# RFFE.net
KiCad netlist of a schematic drawn in Altium Designer
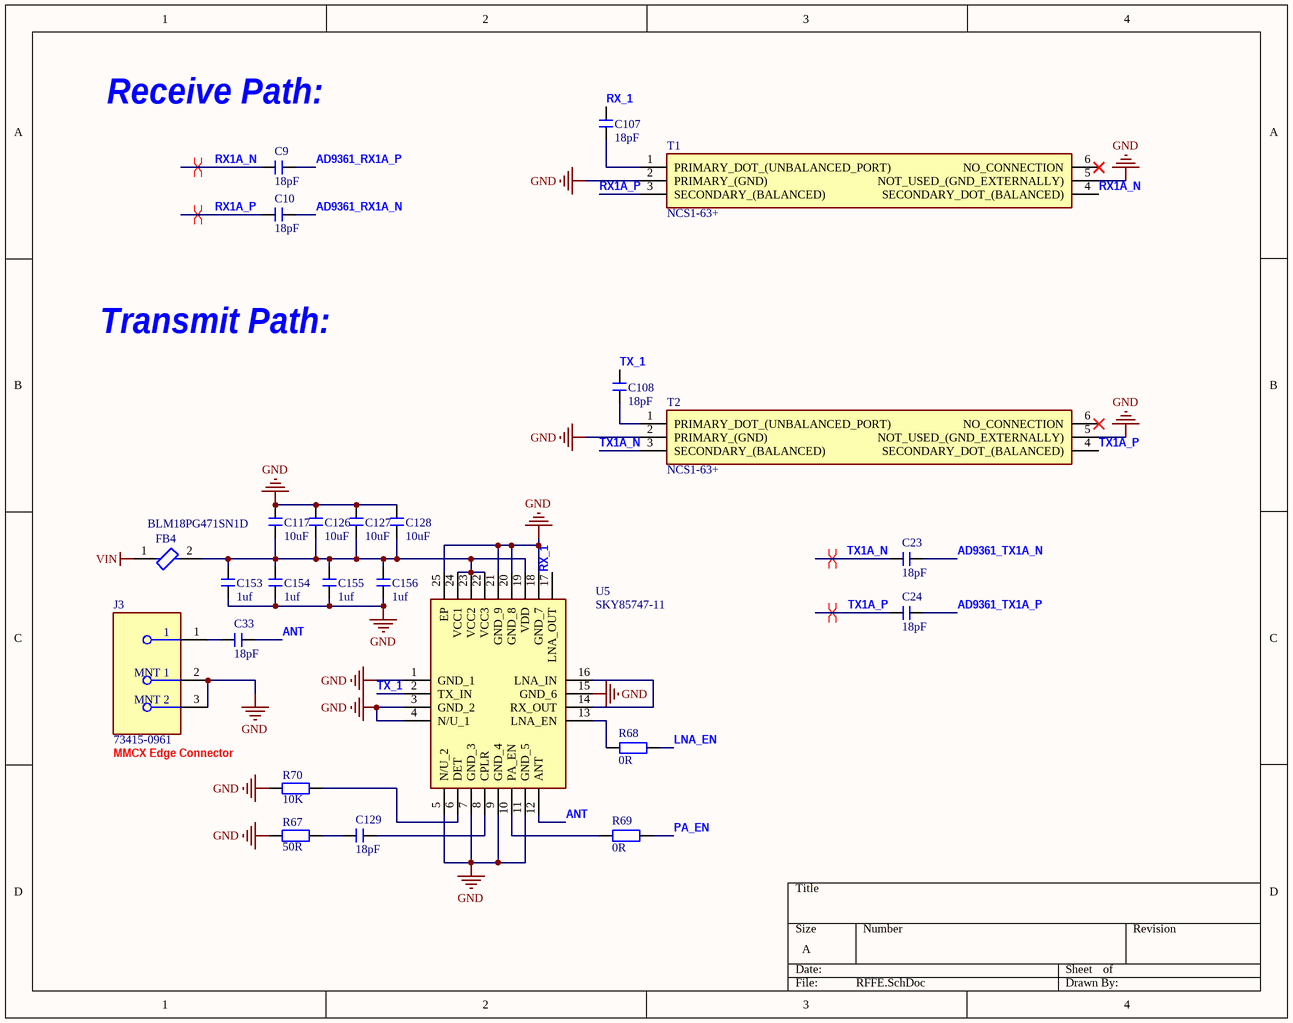
[diagram p0: RFFE.SchDoc]

(export (version "E")
  (design (tool "Eeschema 10.0.6"))
  (components
    (comp (ref "C9")
      (value "18pF")
      (footprint "SamacSys:CAP_0201")
      (description "无极性贴片电容")
      (fields (field (name "版权归属") "源创客"))
      (libsource (lib "源创客") (part "C"))
    )
    (comp (ref "C10")
      (value "18pF")
      (footprint "SamacSys:CAP_0201")
      (description "无极性贴片电容")
      (fields (field (name "版权归属") "源创客"))
      (libsource (lib "源创客") (part "C"))
    )
    (comp (ref "C23")
      (value "18pF")
      (footprint "SamacSys:CAP_0201")
      (description "无极性贴片电容")
      (fields (field (name "版权归属") "源创客"))
      (libsource (lib "源创客") (part "C"))
    )
    (comp (ref "C24")
      (value "18pF")
      (footprint "SamacSys:CAP_0201")
      (description "无极性贴片电容")
      (fields (field (name "版权归属") "源创客"))
      (libsource (lib "源创客") (part "C"))
    )
    (comp (ref "C33")
      (value "18pF")
      (footprint "SamacSys:CAP_0201")
      (description "无极性贴片电容")
      (fields (field (name "版权归属") "源创客"))
      (libsource (lib "源创客") (part "C"))
    )
    (comp (ref "C107")
      (value "18pF")
      (footprint "SamacSys:CAP_0201")
      (description "无极性贴片电容")
      (fields (field (name "版权归属") "源创客"))
      (libsource (lib "源创客") (part "C"))
    )
    (comp (ref "C108")
      (value "18pF")
      (footprint "SamacSys:CAP_0201")
      (description "无极性贴片电容")
      (fields (field (name "版权归属") "源创客"))
      (libsource (lib "源创客") (part "C"))
    )
    (comp (ref "C117")
      (value "10uF")
      (footprint "SamacSys:CAP_0402")
      (description "无极性贴片电容")
      (fields (field (name "版权归属") "源创客"))
      (libsource (lib "源创客") (part "C"))
    )
    (comp (ref "C126")
      (value "10uF")
      (footprint "SamacSys:CAP_0402")
      (description "无极性贴片电容")
      (fields (field (name "版权归属") "源创客"))
      (libsource (lib "源创客") (part "C"))
    )
    (comp (ref "C127")
      (value "10uF")
      (footprint "SamacSys:CAP_0402")
      (description "无极性贴片电容")
      (fields (field (name "版权归属") "源创客"))
      (libsource (lib "源创客") (part "C"))
    )
    (comp (ref "C128")
      (value "10uF")
      (footprint "SamacSys:CAP_0402")
      (description "无极性贴片电容")
      (fields (field (name "版权归属") "源创客"))
      (libsource (lib "源创客") (part "C"))
    )
    (comp (ref "C129")
      (value "18pF")
      (footprint "SamacSys:CAP_0201")
      (description "无极性贴片电容")
      (fields (field (name "版权归属") "源创客"))
      (libsource (lib "源创客") (part "C"))
    )
    (comp (ref "C153")
      (value "1uf")
      (footprint "SamacSys:CAP_0201")
      (description "无极性贴片电容")
      (fields (field (name "版权归属") "源创客"))
      (libsource (lib "源创客") (part "C"))
    )
    (comp (ref "C154")
      (value "1uf")
      (footprint "SamacSys:CAP_0201")
      (description "无极性贴片电容")
      (fields (field (name "版权归属") "源创客"))
      (libsource (lib "源创客") (part "C"))
    )
    (comp (ref "C155")
      (value "1uf")
      (footprint "SamacSys:CAP_0201")
      (description "无极性贴片电容")
      (fields (field (name "版权归属") "源创客"))
      (libsource (lib "源创客") (part "C"))
    )
    (comp (ref "C156")
      (value "1uf")
      (footprint "SamacSys:CAP_0201")
      (description "无极性贴片电容")
      (fields (field (name "版权归属") "源创客"))
      (libsource (lib "源创客") (part "C"))
    )
    (comp (ref "FB4")
      (value "BLM18PG471SN1D")
      (footprint "FP-BLM18-0_15-t0_8-MFG")
      (description "Chip Ferrite Bead, 0603, 470Ω @ 100MHz, 0.2Ω, 25%, 1A")
      (fields (field (name "TOLERANCE") "25%"))
      (libsource (lib "Altium Content Vault") (part "5f30dd21d616792df468990f7003faa"))
    )
    (comp (ref "J3")
      (value "73415-0961")
      (footprint "FP-73415-0961-MFG")
      (libsource (lib "Altium Content Vault") (part "89929399afe843c8b6880c6cbd0f99a"))
    )
    (comp (ref "R67")
      (value "50R")
      (footprint "SamacSys:RES_0201")
      (description "Resistor")
      (libsource (lib "源创客") (part "Resistor"))
    )
    (comp (ref "R68")
      (value "0R")
      (footprint "SamacSys:RES_0402")
      (description "贴片电阻")
      (fields (field (name "版权归属") "源创客"))
      (libsource (lib "源创客") (part "R"))
    )
    (comp (ref "R69")
      (value "0R")
      (footprint "SamacSys:RES_0402")
      (description "贴片电阻")
      (fields (field (name "版权归属") "源创客"))
      (libsource (lib "源创客") (part "R"))
    )
    (comp (ref "R70")
      (value "10K")
      (footprint "SamacSys:RES_0201")
      (description "Resistor")
      (libsource (lib "源创客") (part "Resistor"))
    )
    (comp (ref "T1")
      (value "NCS1-63+")
      (footprint "SamacSys:NCS163")
      (description "Transformer")
      (fields (field (name "MOUSER PART NUMBER") "139-NCS1-63"))
      (libsource (lib "*") (part "NCS1-63+"))
    )
    (comp (ref "T2")
      (value "NCS1-63+")
      (footprint "SamacSys:NCS163")
      (description "Transformer")
      (fields (field (name "MOUSER PART NUMBER") "139-NCS1-63"))
      (libsource (lib "*") (part "NCS1-63+"))
    )
    (comp (ref "U5")
      (value "SKY85747-11")
      (footprint "SamacSys:SKY8574711")
      (description "Integrated Circuit")
      (libsource (lib "*") (part "SKY85747-11"))
    )
  )
  (nets
    (net (code "1") (name "/AD9361_RX1A_N") (class "Default")
      (node (ref "C10") (pin "2") (pinfunction "2_2") (pintype "passive"))
    )
    (net (code "2") (name "/AD9361_RX1A_P") (class "Default")
      (node (ref "C9") (pin "2") (pinfunction "2_2") (pintype "passive"))
    )
    (net (code "3") (name "/AD9361_TX1A_N") (class "Default")
      (node (ref "C23") (pin "2") (pinfunction "2_2") (pintype "passive"))
    )
    (net (code "4") (name "/AD9361_TX1A_P") (class "Default")
      (node (ref "C24") (pin "2") (pinfunction "2_2") (pintype "passive"))
    )
    (net (code "5") (name "/ANT") (class "Default")
      (node (ref "C33") (pin "2") (pinfunction "2_2") (pintype "passive"))
      (node (ref "U5") (pin "12") (pinfunction "ANT_12") (pintype "passive"))
    )
    (net (code "6") (name "/LNA_EN") (class "Default")
      (node (ref "R68") (pin "1") (pinfunction "1_1") (pintype "passive"))
    )
    (net (code "7") (name "/PA_EN") (class "Default")
      (node (ref "R69") (pin "1") (pinfunction "1_1") (pintype "passive"))
    )
    (net (code "8") (name "/RX1A_N") (class "Default")
      (node (ref "C9") (pin "1") (pinfunction "1_1") (pintype "passive"))
      (node (ref "T1") (pin "4") (pinfunction "SECONDARY_DOT_(BALANCED)_4") (pintype "passive"))
    )
    (net (code "9") (name "/RX1A_P") (class "Default")
      (node (ref "C10") (pin "1") (pinfunction "1_1") (pintype "passive"))
      (node (ref "T1") (pin "3") (pinfunction "SECONDARY_(BALANCED)_3") (pintype "passive"))
    )
    (net (code "10") (name "/RX_1") (class "Default")
      (node (ref "C107") (pin "2") (pinfunction "2_2") (pintype "passive"))
      (node (ref "U5") (pin "17") (pinfunction "LNA_OUT_17") (pintype "passive"))
    )
    (net (code "11") (name "/TX1A_N") (class "Default")
      (node (ref "C23") (pin "1") (pinfunction "1_1") (pintype "passive"))
      (node (ref "T2") (pin "3") (pinfunction "SECONDARY_(BALANCED)_3") (pintype "passive"))
    )
    (net (code "12") (name "/TX1A_P") (class "Default")
      (node (ref "C24") (pin "1") (pinfunction "1_1") (pintype "passive"))
      (node (ref "T2") (pin "4") (pinfunction "SECONDARY_DOT_(BALANCED)_4") (pintype "passive"))
    )
    (net (code "13") (name "/TX_1") (class "Default")
      (node (ref "C108") (pin "2") (pinfunction "2_2") (pintype "passive"))
      (node (ref "U5") (pin "2") (pinfunction "TX_IN_2") (pintype "passive"))
    )
    (net (code "14") (name "GND") (class "Default")
      (node (ref "C117") (pin "2") (pinfunction "2_2") (pintype "passive"))
      (node (ref "C126") (pin "2") (pinfunction "2_2") (pintype "passive"))
      (node (ref "C127") (pin "2") (pinfunction "2_2") (pintype "passive"))
      (node (ref "C128") (pin "2") (pinfunction "2_2") (pintype "passive"))
      (node (ref "C153") (pin "1") (pinfunction "1_1") (pintype "passive"))
      (node (ref "C154") (pin "1") (pinfunction "1_1") (pintype "passive"))
      (node (ref "C155") (pin "1") (pinfunction "1_1") (pintype "passive"))
      (node (ref "C156") (pin "1") (pinfunction "1_1") (pintype "passive"))
      (node (ref "J3") (pin "2") (pinfunction "MNT_1_2") (pintype "passive"))
      (node (ref "J3") (pin "3") (pinfunction "MNT_2_3") (pintype "passive"))
      (node (ref "R67") (pin "2") (pinfunction "2_2") (pintype "passive"))
      (node (ref "R70") (pin "2") (pinfunction "2_2") (pintype "passive"))
      (node (ref "T1") (pin "2") (pinfunction "PRIMARY_(GND)_2") (pintype "passive"))
      (node (ref "T1") (pin "5") (pinfunction "NOT_USED_(GND_EXTERNALLY)_5") (pintype "passive"))
      (node (ref "T2") (pin "2") (pinfunction "PRIMARY_(GND)_2") (pintype "passive"))
      (node (ref "T2") (pin "5") (pinfunction "NOT_USED_(GND_EXTERNALLY)_5") (pintype "passive"))
      (node (ref "U5") (pin "1") (pinfunction "GND_1_1") (pintype "passive"))
      (node (ref "U5") (pin "11") (pinfunction "GND_5_11") (pintype "passive"))
      (node (ref "U5") (pin "15") (pinfunction "GND_6_15") (pintype "passive"))
      (node (ref "U5") (pin "18") (pinfunction "GND_7_18") (pintype "passive"))
      (node (ref "U5") (pin "20") (pinfunction "GND_8_20") (pintype "passive"))
      (node (ref "U5") (pin "21") (pinfunction "GND_9_21") (pintype "passive"))
      (node (ref "U5") (pin "25") (pinfunction "EP_25") (pintype "passive"))
      (node (ref "U5") (pin "3") (pinfunction "GND_2_3") (pintype "passive"))
      (node (ref "U5") (pin "4") (pinfunction "N/U_1_4") (pintype "passive"))
      (node (ref "U5") (pin "5") (pinfunction "N/U_2_5") (pintype "passive"))
      (node (ref "U5") (pin "7") (pinfunction "GND_3_7") (pintype "passive"))
      (node (ref "U5") (pin "9") (pinfunction "GND_4_9") (pintype "passive"))
    )
    (net (code "15") (name "Net-(C33-Pad1)") (class "Default")
      (node (ref "C33") (pin "1") (pinfunction "1_1") (pintype "passive"))
      (node (ref "J3") (pin "1") (pinfunction "1_1") (pintype "passive"))
    )
    (net (code "16") (name "Net-(C129-Pad1)") (class "Default")
      (node (ref "C129") (pin "1") (pinfunction "1_1") (pintype "passive"))
      (node (ref "R67") (pin "1") (pinfunction "1_1") (pintype "passive"))
    )
    (net (code "17") (name "Net-(T1-PRIMARY_DOT_(UNBALANCED_PORT))") (class "Default")
      (node (ref "C107") (pin "1") (pinfunction "1_1") (pintype "passive"))
      (node (ref "T1") (pin "1") (pinfunction "PRIMARY_DOT_(UNBALANCED_PORT)_1") (pintype "passive"))
    )
    (net (code "18") (name "Net-(T2-PRIMARY_DOT_(UNBALANCED_PORT))") (class "Default")
      (node (ref "C108") (pin "1") (pinfunction "1_1") (pintype "passive"))
      (node (ref "T2") (pin "1") (pinfunction "PRIMARY_DOT_(UNBALANCED_PORT)_1") (pintype "passive"))
    )
    (net (code "19") (name "Net-(U5-CPLR)") (class "Default")
      (node (ref "C129") (pin "2") (pinfunction "2_2") (pintype "passive"))
      (node (ref "U5") (pin "8") (pinfunction "CPLR_8") (pintype "passive"))
    )
    (net (code "20") (name "Net-(U5-DET)") (class "Default")
      (node (ref "R70") (pin "1") (pinfunction "1_1") (pintype "passive"))
      (node (ref "U5") (pin "6") (pinfunction "DET_6") (pintype "passive"))
    )
    (net (code "21") (name "Net-(U5-LNA_EN)") (class "Default")
      (node (ref "R68") (pin "2") (pinfunction "2_2") (pintype "passive"))
      (node (ref "U5") (pin "13") (pinfunction "LNA_EN_13") (pintype "passive"))
    )
    (net (code "22") (name "Net-(U5-LNA_IN)") (class "Default")
      (node (ref "U5") (pin "14") (pinfunction "RX_OUT_14") (pintype "passive"))
      (node (ref "U5") (pin "16") (pinfunction "LNA_IN_16") (pintype "passive"))
    )
    (net (code "23") (name "Net-(U5-PA_EN)") (class "Default")
      (node (ref "R69") (pin "2") (pinfunction "2_2") (pintype "passive"))
      (node (ref "U5") (pin "10") (pinfunction "PA_EN_10") (pintype "passive"))
    )
    (net (code "24") (name "Net-(U5-VCC1)") (class "Default")
      (node (ref "C117") (pin "1") (pinfunction "1_1") (pintype "passive"))
      (node (ref "C126") (pin "1") (pinfunction "1_1") (pintype "passive"))
      (node (ref "C127") (pin "1") (pinfunction "1_1") (pintype "passive"))
      (node (ref "C128") (pin "1") (pinfunction "1_1") (pintype "passive"))
      (node (ref "C153") (pin "2") (pinfunction "2_2") (pintype "passive"))
      (node (ref "C154") (pin "2") (pinfunction "2_2") (pintype "passive"))
      (node (ref "C155") (pin "2") (pinfunction "2_2") (pintype "passive"))
      (node (ref "C156") (pin "2") (pinfunction "2_2") (pintype "passive"))
      (node (ref "FB4") (pin "2") (pinfunction "2_2") (pintype "passive"))
      (node (ref "U5") (pin "19") (pinfunction "VDD_19") (pintype "passive"))
      (node (ref "U5") (pin "22") (pinfunction "VCC3_22") (pintype "passive"))
      (node (ref "U5") (pin "23") (pinfunction "VCC2_23") (pintype "passive"))
      (node (ref "U5") (pin "24") (pinfunction "VCC1_24") (pintype "passive"))
    )
    (net (code "25") (name "VIN") (class "Default")
      (node (ref "FB4") (pin "1") (pinfunction "1_1") (pintype "passive"))
    )
    (net (code "26") (name "unconnected-(T1-NO_CONNECTION-Pad6)") (class "Default")
      (node (ref "T1") (pin "6") (pinfunction "NO_CONNECTION_6") (pintype "passive+no_connect"))
    )
    (net (code "27") (name "unconnected-(T2-NO_CONNECTION-Pad6)") (class "Default")
      (node (ref "T2") (pin "6") (pinfunction "NO_CONNECTION_6") (pintype "passive+no_connect"))
    )
  )
)
